# Power.net
KiCad netlist of a schematic drawn in Altium Designer
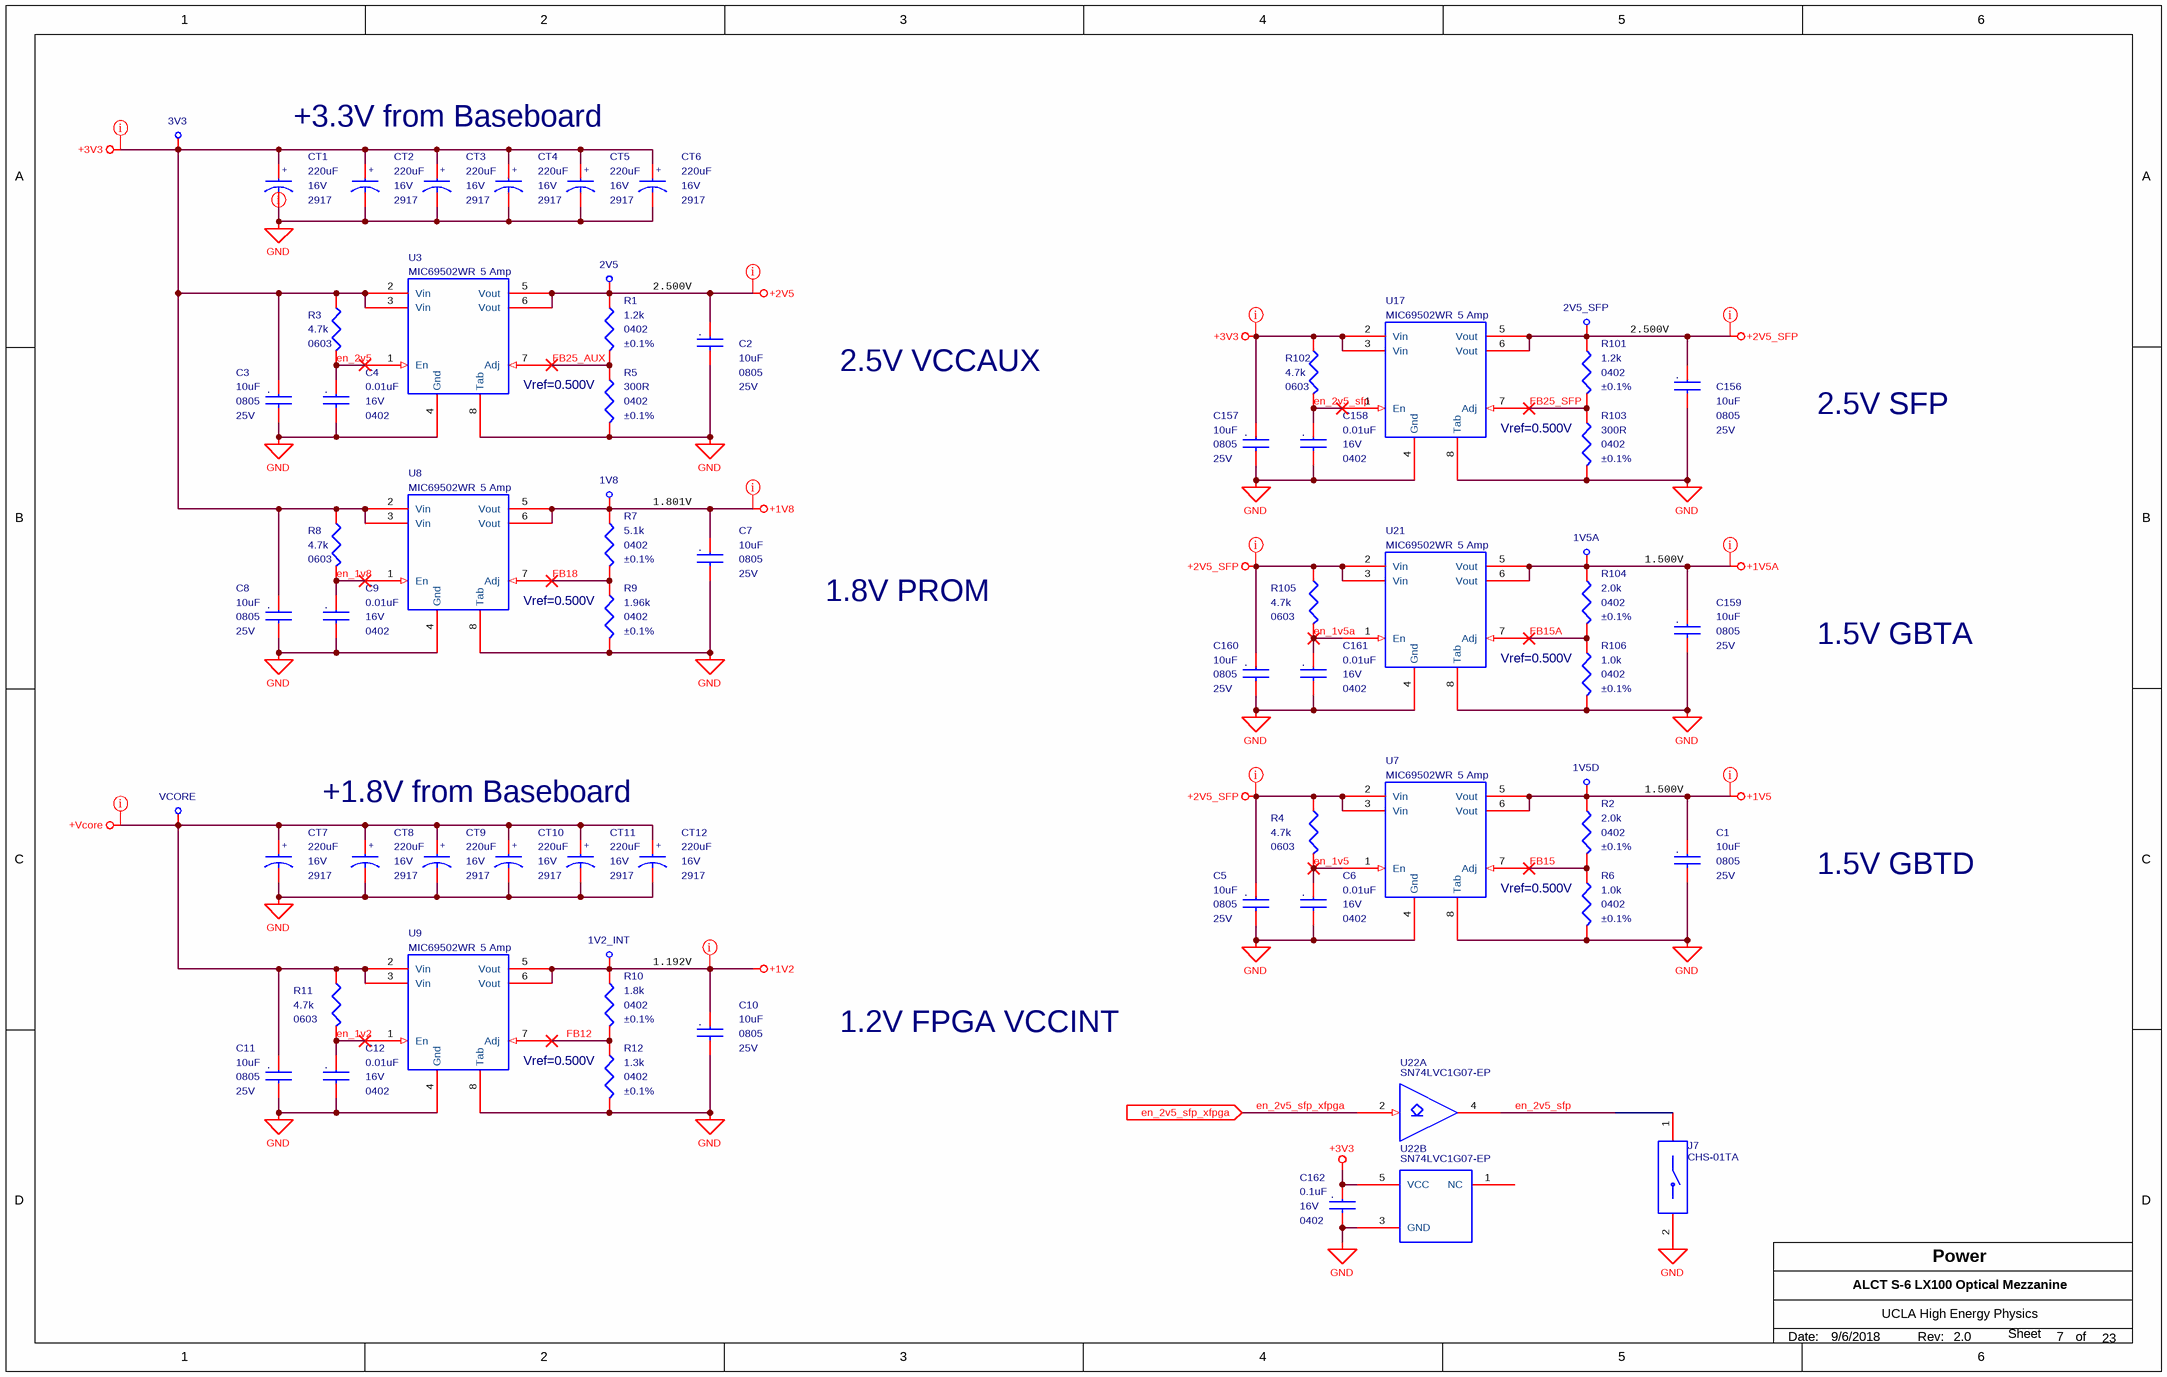
[diagram p0: Power.SchDoc]

(export (version "E")
  (design (tool "Eeschema 10.0.6"))
  (components
    (comp (ref "1V2_INT")
      (value "Test Point Via")
      (footprint "MC_S6/TH/TPVIA")
      (libsource (lib "ALCT_MEZ_SPARTAN6_Library") (part "TPVIA"))
    )
    (comp (ref "1V5A")
      (value "Test Point Via")
      (footprint "MC_S6/TH/TPVIA")
      (libsource (lib "ALCT_MEZ_SPARTAN6_Library") (part "TPVIA"))
    )
    (comp (ref "1V5D")
      (value "Test Point Via")
      (footprint "MC_S6/TH/TPVIA")
      (libsource (lib "ALCT_MEZ_SPARTAN6_Library") (part "TPVIA"))
    )
    (comp (ref "1V8")
      (value "Test Point Via")
      (footprint "MC_S6/TH/TPVIA")
      (libsource (lib "ALCT_MEZ_SPARTAN6_Library") (part "TPVIA"))
    )
    (comp (ref "2V5")
      (value "Test Point Via")
      (footprint "MC_S6/TH/TPVIA")
      (libsource (lib "ALCT_MEZ_SPARTAN6_Library") (part "TPVIA"))
    )
    (comp (ref "2V5_SFP")
      (value "Test Point Via")
      (footprint "MC_S6/TH/TPVIA")
      (libsource (lib "ALCT_MEZ_SPARTAN6_Library") (part "TPVIA"))
    )
    (comp (ref "3V3")
      (value "Test Point Via")
      (footprint "MC_S6/TH/TPVIA")
      (libsource (lib "ALCT_MEZ_SPARTAN6_Library") (part "TPVIA"))
    )
    (comp (ref "C1")
      (value "10uF")
      (footprint "MC_S6/SM/C_0805_IPC")
      (description "CAP CER 10UF 25V X5R 0805")
      (fields
        (field (name "MANUFACTURER") "Murata Electronics North America")
        (field (name "MANUFACTURER PART NUMBER") "GRM21BR61E106KA73L")
        (field (name "VOLTAGE - RATED") "25V")
        (field (name "PACKAGE") "0805")
      )
      (libsource (lib "ALCT_MEZ_SPARTAN6_Library") (part "GRM21BR61E106KA73L"))
    )
    (comp (ref "C2")
      (value "10uF")
      (footprint "MC_S6/SM/C_0805_IPC")
      (description "CAP CER 10UF 25V X5R 0805")
      (fields
        (field (name "MANUFACTURER") "Murata Electronics North America")
        (field (name "MANUFACTURER PART NUMBER") "GRM21BR61E106KA73L")
        (field (name "VOLTAGE - RATED") "25V")
        (field (name "PACKAGE") "0805")
      )
      (libsource (lib "ALCT_MEZ_SPARTAN6_Library") (part "GRM21BR61E106KA73L"))
    )
    (comp (ref "C3")
      (value "10uF")
      (footprint "MC_S6/SM/C_0805_IPC")
      (description "CAP CER 10UF 25V X5R 0805")
      (fields
        (field (name "MANUFACTURER") "Murata Electronics North America")
        (field (name "MANUFACTURER PART NUMBER") "GRM21BR61E106KA73L")
        (field (name "VOLTAGE - RATED") "25V")
        (field (name "PACKAGE") "0805")
      )
      (libsource (lib "ALCT_MEZ_SPARTAN6_Library") (part "GRM21BR61E106KA73L"))
    )
    (comp (ref "C4")
      (value "0.01uF")
      (footprint "MC_S6/SM/C_0402_IPC")
      (description "CAP CER 10nF 16V X7R 0402")
      (fields
        (field (name "MANUFACTURER") "KEMET")
        (field (name "MANUFACTURER PART NUMBER") "C0402C103K4RACTU")
        (field (name "VOLTAGE - RATED") "16V")
        (field (name "PACKAGE") "0402")
      )
      (libsource (lib "ALCT_MEZ_SPARTAN6_Library") (part "C0402C103K4RACTU"))
    )
    (comp (ref "C5")
      (value "10uF")
      (footprint "MC_S6/SM/C_0805_IPC")
      (description "CAP CER 10UF 25V X5R 0805")
      (fields
        (field (name "MANUFACTURER") "Murata Electronics North America")
        (field (name "MANUFACTURER PART NUMBER") "GRM21BR61E106KA73L")
        (field (name "VOLTAGE - RATED") "25V")
        (field (name "PACKAGE") "0805")
      )
      (libsource (lib "ALCT_MEZ_SPARTAN6_Library") (part "GRM21BR61E106KA73L"))
    )
    (comp (ref "C6")
      (value "0.01uF")
      (footprint "MC_S6/SM/C_0402_IPC")
      (description "CAP CER 10nF 16V X7R 0402")
      (fields
        (field (name "MANUFACTURER") "KEMET")
        (field (name "MANUFACTURER PART NUMBER") "C0402C103K4RACTU")
        (field (name "VOLTAGE - RATED") "16V")
        (field (name "PACKAGE") "0402")
      )
      (libsource (lib "ALCT_MEZ_SPARTAN6_Library") (part "C0402C103K4RACTU"))
    )
    (comp (ref "C7")
      (value "10uF")
      (footprint "MC_S6/SM/C_0805_IPC")
      (description "CAP CER 10UF 25V X5R 0805")
      (fields
        (field (name "MANUFACTURER") "Murata Electronics North America")
        (field (name "MANUFACTURER PART NUMBER") "GRM21BR61E106KA73L")
        (field (name "VOLTAGE - RATED") "25V")
        (field (name "PACKAGE") "0805")
      )
      (libsource (lib "ALCT_MEZ_SPARTAN6_Library") (part "GRM21BR61E106KA73L"))
    )
    (comp (ref "C8")
      (value "10uF")
      (footprint "MC_S6/SM/C_0805_IPC")
      (description "CAP CER 10UF 25V X5R 0805")
      (fields
        (field (name "MANUFACTURER") "Murata Electronics North America")
        (field (name "MANUFACTURER PART NUMBER") "GRM21BR61E106KA73L")
        (field (name "VOLTAGE - RATED") "25V")
        (field (name "PACKAGE") "0805")
      )
      (libsource (lib "ALCT_MEZ_SPARTAN6_Library") (part "GRM21BR61E106KA73L"))
    )
    (comp (ref "C9")
      (value "0.01uF")
      (footprint "MC_S6/SM/C_0402_IPC")
      (description "CAP CER 10nF 16V X7R 0402")
      (fields
        (field (name "MANUFACTURER") "KEMET")
        (field (name "MANUFACTURER PART NUMBER") "C0402C103K4RACTU")
        (field (name "VOLTAGE - RATED") "16V")
        (field (name "PACKAGE") "0402")
      )
      (libsource (lib "ALCT_MEZ_SPARTAN6_Library") (part "C0402C103K4RACTU"))
    )
    (comp (ref "C10")
      (value "10uF")
      (footprint "MC_S6/SM/C_0805_IPC")
      (description "CAP CER 10UF 25V X5R 0805")
      (fields
        (field (name "MANUFACTURER") "Murata Electronics North America")
        (field (name "MANUFACTURER PART NUMBER") "GRM21BR61E106KA73L")
        (field (name "VOLTAGE - RATED") "25V")
        (field (name "PACKAGE") "0805")
      )
      (libsource (lib "ALCT_MEZ_SPARTAN6_Library") (part "GRM21BR61E106KA73L"))
    )
    (comp (ref "C11")
      (value "10uF")
      (footprint "MC_S6/SM/C_0805_IPC")
      (description "CAP CER 10UF 25V X5R 0805")
      (fields
        (field (name "MANUFACTURER") "Murata Electronics North America")
        (field (name "MANUFACTURER PART NUMBER") "GRM21BR61E106KA73L")
        (field (name "VOLTAGE - RATED") "25V")
        (field (name "PACKAGE") "0805")
      )
      (libsource (lib "ALCT_MEZ_SPARTAN6_Library") (part "GRM21BR61E106KA73L"))
    )
    (comp (ref "C12")
      (value "0.01uF")
      (footprint "MC_S6/SM/C_0402_IPC")
      (description "CAP CER 10nF 16V X7R 0402")
      (fields
        (field (name "MANUFACTURER") "KEMET")
        (field (name "MANUFACTURER PART NUMBER") "C0402C103K4RACTU")
        (field (name "VOLTAGE - RATED") "16V")
        (field (name "PACKAGE") "0402")
      )
      (libsource (lib "ALCT_MEZ_SPARTAN6_Library") (part "C0402C103K4RACTU"))
    )
    (comp (ref "C156")
      (value "10uF")
      (footprint "MC_S6/SM/C_0805_IPC")
      (description "CAP CER 10UF 25V X5R 0805")
      (fields
        (field (name "MANUFACTURER") "Murata Electronics North America")
        (field (name "MANUFACTURER PART NUMBER") "GRM21BR61E106KA73L")
        (field (name "VOLTAGE - RATED") "25V")
        (field (name "PACKAGE") "0805")
      )
      (libsource (lib "ALCT_MEZ_SPARTAN6_Library") (part "GRM21BR61E106KA73L"))
    )
    (comp (ref "C157")
      (value "10uF")
      (footprint "MC_S6/SM/C_0805_IPC")
      (description "CAP CER 10UF 25V X5R 0805")
      (fields
        (field (name "MANUFACTURER") "Murata Electronics North America")
        (field (name "MANUFACTURER PART NUMBER") "GRM21BR61E106KA73L")
        (field (name "VOLTAGE - RATED") "25V")
        (field (name "PACKAGE") "0805")
      )
      (libsource (lib "ALCT_MEZ_SPARTAN6_Library") (part "GRM21BR61E106KA73L"))
    )
    (comp (ref "C158")
      (value "0.01uF")
      (footprint "MC_S6/SM/C_0402_IPC")
      (description "CAP CER 10nF 16V X7R 0402")
      (fields
        (field (name "MANUFACTURER") "KEMET")
        (field (name "MANUFACTURER PART NUMBER") "C0402C103K4RACTU")
        (field (name "VOLTAGE - RATED") "16V")
        (field (name "PACKAGE") "0402")
      )
      (libsource (lib "ALCT_MEZ_SPARTAN6_Library") (part "C0402C103K4RACTU"))
    )
    (comp (ref "C159")
      (value "10uF")
      (footprint "MC_S6/SM/C_0805_IPC")
      (description "CAP CER 10UF 25V X5R 0805")
      (fields
        (field (name "MANUFACTURER") "Murata Electronics North America")
        (field (name "MANUFACTURER PART NUMBER") "GRM21BR61E106KA73L")
        (field (name "VOLTAGE - RATED") "25V")
        (field (name "PACKAGE") "0805")
      )
      (libsource (lib "ALCT_MEZ_SPARTAN6_Library") (part "GRM21BR61E106KA73L"))
    )
    (comp (ref "C160")
      (value "10uF")
      (footprint "MC_S6/SM/C_0805_IPC")
      (description "CAP CER 10UF 25V X5R 0805")
      (fields
        (field (name "MANUFACTURER") "Murata Electronics North America")
        (field (name "MANUFACTURER PART NUMBER") "GRM21BR61E106KA73L")
        (field (name "VOLTAGE - RATED") "25V")
        (field (name "PACKAGE") "0805")
      )
      (libsource (lib "ALCT_MEZ_SPARTAN6_Library") (part "GRM21BR61E106KA73L"))
    )
    (comp (ref "C161")
      (value "0.01uF")
      (footprint "MC_S6/SM/C_0402_IPC")
      (description "CAP CER 10nF 16V X7R 0402")
      (fields
        (field (name "MANUFACTURER") "KEMET")
        (field (name "MANUFACTURER PART NUMBER") "C0402C103K4RACTU")
        (field (name "VOLTAGE - RATED") "16V")
        (field (name "PACKAGE") "0402")
      )
      (libsource (lib "ALCT_MEZ_SPARTAN6_Library") (part "C0402C103K4RACTU"))
    )
    (comp (ref "C162")
      (value "0.1uF")
      (footprint "MC_S6/SM/C_0402_IPC")
      (description "CAP CER 0.1UF 16V X7R 0402")
      (fields
        (field (name "MANUFACTURER") "KEMET")
        (field (name "MANUFACTURER PART NUMBER") "C0402C104K4RACTU")
        (field (name "PACKAGE") "0402")
        (field (name "VOLTAGE - RATED") "16V")
      )
      (libsource (lib "ALCT_MEZ_SPARTAN6_Library") (part "C0402C104K4RACTU"))
    )
    (comp (ref "CT1")
      (value "220uF")
      (footprint "MC_S6/SM/CT_2917_D")
      (description "CAP TANT 220UF 16V 10% 2917")
      (fields
        (field (name "MANUFACTURER") "KEMET")
        (field (name "MANUFACTURER PART NUMBER") "T491D227K016AT")
        (field (name "VOLTAGE - RATED") "16V")
        (field (name "PACKAGE") "2917")
      )
      (libsource (lib "ALCT_MEZ_SPARTAN6_Library") (part "T491D227K016AT"))
    )
    (comp (ref "CT2")
      (value "220uF")
      (footprint "MC_S6/SM/CT_2917_D")
      (description "CAP TANT 220UF 16V 10% 2917")
      (fields
        (field (name "MANUFACTURER") "KEMET")
        (field (name "MANUFACTURER PART NUMBER") "T491D227K016AT")
        (field (name "VOLTAGE - RATED") "16V")
        (field (name "PACKAGE") "2917")
      )
      (libsource (lib "ALCT_MEZ_SPARTAN6_Library") (part "T491D227K016AT"))
    )
    (comp (ref "CT3")
      (value "220uF")
      (footprint "MC_S6/SM/CT_2917_D")
      (description "CAP TANT 220UF 16V 10% 2917")
      (fields
        (field (name "MANUFACTURER") "KEMET")
        (field (name "MANUFACTURER PART NUMBER") "T491D227K016AT")
        (field (name "VOLTAGE - RATED") "16V")
        (field (name "PACKAGE") "2917")
      )
      (libsource (lib "ALCT_MEZ_SPARTAN6_Library") (part "T491D227K016AT"))
    )
    (comp (ref "CT4")
      (value "220uF")
      (footprint "MC_S6/SM/CT_2917_D")
      (description "CAP TANT 220UF 16V 10% 2917")
      (fields
        (field (name "MANUFACTURER") "KEMET")
        (field (name "MANUFACTURER PART NUMBER") "T491D227K016AT")
        (field (name "VOLTAGE - RATED") "16V")
        (field (name "PACKAGE") "2917")
      )
      (libsource (lib "ALCT_MEZ_SPARTAN6_Library") (part "T491D227K016AT"))
    )
    (comp (ref "CT5")
      (value "220uF")
      (footprint "MC_S6/SM/CT_2917_D")
      (description "CAP TANT 220UF 16V 10% 2917")
      (fields
        (field (name "MANUFACTURER") "KEMET")
        (field (name "MANUFACTURER PART NUMBER") "T491D227K016AT")
        (field (name "VOLTAGE - RATED") "16V")
        (field (name "PACKAGE") "2917")
      )
      (libsource (lib "ALCT_MEZ_SPARTAN6_Library") (part "T491D227K016AT"))
    )
    (comp (ref "CT6")
      (value "220uF")
      (footprint "MC_S6/SM/CT_2917_D")
      (description "CAP TANT 220UF 16V 10% 2917")
      (fields
        (field (name "MANUFACTURER") "KEMET")
        (field (name "MANUFACTURER PART NUMBER") "T491D227K016AT")
        (field (name "VOLTAGE - RATED") "16V")
        (field (name "PACKAGE") "2917")
      )
      (libsource (lib "ALCT_MEZ_SPARTAN6_Library") (part "T491D227K016AT"))
    )
    (comp (ref "CT7")
      (value "220uF")
      (footprint "MC_S6/SM/CT_2917_D")
      (description "CAP TANT 220UF 16V 10% 2917")
      (fields
        (field (name "MANUFACTURER") "KEMET")
        (field (name "MANUFACTURER PART NUMBER") "T491D227K016AT")
        (field (name "VOLTAGE - RATED") "16V")
        (field (name "PACKAGE") "2917")
      )
      (libsource (lib "ALCT_MEZ_SPARTAN6_Library") (part "T491D227K016AT"))
    )
    (comp (ref "CT8")
      (value "220uF")
      (footprint "MC_S6/SM/CT_2917_D")
      (description "CAP TANT 220UF 16V 10% 2917")
      (fields
        (field (name "MANUFACTURER") "KEMET")
        (field (name "MANUFACTURER PART NUMBER") "T491D227K016AT")
        (field (name "VOLTAGE - RATED") "16V")
        (field (name "PACKAGE") "2917")
      )
      (libsource (lib "ALCT_MEZ_SPARTAN6_Library") (part "T491D227K016AT"))
    )
    (comp (ref "CT9")
      (value "220uF")
      (footprint "MC_S6/SM/CT_2917_D")
      (description "CAP TANT 220UF 16V 10% 2917")
      (fields
        (field (name "MANUFACTURER") "KEMET")
        (field (name "MANUFACTURER PART NUMBER") "T491D227K016AT")
        (field (name "VOLTAGE - RATED") "16V")
        (field (name "PACKAGE") "2917")
      )
      (libsource (lib "ALCT_MEZ_SPARTAN6_Library") (part "T491D227K016AT"))
    )
    (comp (ref "CT10")
      (value "220uF")
      (footprint "MC_S6/SM/CT_2917_D")
      (description "CAP TANT 220UF 16V 10% 2917")
      (fields
        (field (name "MANUFACTURER") "KEMET")
        (field (name "MANUFACTURER PART NUMBER") "T491D227K016AT")
        (field (name "VOLTAGE - RATED") "16V")
        (field (name "PACKAGE") "2917")
      )
      (libsource (lib "ALCT_MEZ_SPARTAN6_Library") (part "T491D227K016AT"))
    )
    (comp (ref "CT11")
      (value "220uF")
      (footprint "MC_S6/SM/CT_2917_D")
      (description "CAP TANT 220UF 16V 10% 2917")
      (fields
        (field (name "MANUFACTURER") "KEMET")
        (field (name "MANUFACTURER PART NUMBER") "T491D227K016AT")
        (field (name "VOLTAGE - RATED") "16V")
        (field (name "PACKAGE") "2917")
      )
      (libsource (lib "ALCT_MEZ_SPARTAN6_Library") (part "T491D227K016AT"))
    )
    (comp (ref "CT12")
      (value "220uF")
      (footprint "MC_S6/SM/CT_2917_D")
      (description "CAP TANT 220UF 16V 10% 2917")
      (fields
        (field (name "MANUFACTURER") "KEMET")
        (field (name "MANUFACTURER PART NUMBER") "T491D227K016AT")
        (field (name "VOLTAGE - RATED") "16V")
        (field (name "PACKAGE") "2917")
      )
      (libsource (lib "ALCT_MEZ_SPARTAN6_Library") (part "T491D227K016AT"))
    )
    (comp (ref "J7")
      (value "CHS-01TA")
      (footprint "CHS-01TA")
      (description "SWITCH SLIDE DIP SPST 100MA 6V")
      (fields (field (name "MANUFACTURER") "Nidec Copal"))
      (libsource (lib "ALCT_MEZ_SPARTAN6_Library") (part "CHS-01TA"))
    )
    (comp (ref "R1")
      (value "1.2k")
      (footprint "MC_S6/SM/R_0402_IPC")
      (description "RES SMD 1.2K OHM 0.1% 1/16W 0402")
      (fields
        (field (name "TOLERANCE") "±0.1%")
        (field (name "MANUFACTURER") "Panasonic Electronic Components")
        (field (name "MANUFACTURER PART NUMBER") "ERA-2AEB122X")
        (field (name "PACKAGE") "0402")
      )
      (libsource (lib "ALCT_MEZ_SPARTAN6_Library") (part "ERA-2AEB122X"))
    )
    (comp (ref "R2")
      (value "2.0k")
      (footprint "MC_S6/SM/R_0402_IPC")
      (description "RES SMD 2.0K OHM 0.1% 1/16W 0402")
      (fields
        (field (name "TOLERANCE") "±0.1%")
        (field (name "MANUFACTURER") "Panasonic Electronic Components")
        (field (name "MANUFACTURER PART NUMBER") "ERA-2AEB202X")
        (field (name "PACKAGE") "0402")
      )
      (libsource (lib "ALCT_MEZ_SPARTAN6_Library") (part "ERA-2AEB202X"))
    )
    (comp (ref "R3")
      (value "4.7k")
      (footprint "MC_S6/SM/R_0603_IPC")
      (description "RES SMD 4.7K OHM 1% 1/10W 0603")
      (fields
        (field (name "TOLERANCE") "±1%")
        (field (name "MANUFACTURER") "Bourns Inc.")
        (field (name "SUPPLIER DEVICE PACKAGE") "0603")
      )
      (libsource (lib "ALCT_MEZ_SPARTAN6_Library") (part "CR0603-FX-4701ELF"))
    )
    (comp (ref "R4")
      (value "4.7k")
      (footprint "MC_S6/SM/R_0603_IPC")
      (description "RES SMD 4.7K OHM 1% 1/10W 0603")
      (fields
        (field (name "TOLERANCE") "±1%")
        (field (name "MANUFACTURER") "Bourns Inc.")
        (field (name "SUPPLIER DEVICE PACKAGE") "0603")
      )
      (libsource (lib "ALCT_MEZ_SPARTAN6_Library") (part "CR0603-FX-4701ELF"))
    )
    (comp (ref "R5")
      (value "300R")
      (footprint "MC_S6/SM/R_0402_IPC")
      (description "RES SMD 300 OHM 0.1% 1/16W 0402")
      (fields
        (field (name "TOLERANCE") "±0.1%")
        (field (name "MANUFACTURER") "Panasonic Electronic Components")
        (field (name "MANUFACTURER PART NUMBER") "ERA-2AEB301X")
        (field (name "PACKAGE") "0402")
      )
      (libsource (lib "ALCT_MEZ_SPARTAN6_Library") (part "ERA-2AEB301X"))
    )
    (comp (ref "R6")
      (value "1.0k")
      (footprint "MC_S6/SM/R_0402_IPC")
      (description "RES SMD 1.0K OHM 0.1% 1/16W 0402")
      (fields
        (field (name "TOLERANCE") "±0.1%")
        (field (name "MANUFACTURER") "Panasonic Electronic Components")
        (field (name "MANUFACTURER PART NUMBER") "ERA-2AEB102X")
        (field (name "PACKAGE") "0402")
      )
      (libsource (lib "ALCT_MEZ_SPARTAN6_Library") (part "ERA-2AEB102X"))
    )
    (comp (ref "R7")
      (value "5.1k")
      (footprint "MC_S6/SM/R_0402_IPC")
      (description "RES SMD 5.1K OHM 0.1% 1/16W 0402")
      (fields
        (field (name "TOLERANCE") "±0.1%")
        (field (name "MANUFACTURER") "Panasonic Electronic Components")
        (field (name "MANUFACTURER PART NUMBER") "ERA-2AEB512X")
        (field (name "SUPPLIER DEVICE PACKAGE") "0402")
      )
      (libsource (lib "ALCT_MEZ_SPARTAN6_Library") (part "ERA-2AEB512X"))
    )
    (comp (ref "R8")
      (value "4.7k")
      (footprint "MC_S6/SM/R_0603_IPC")
      (description "RES SMD 4.7K OHM 1% 1/10W 0603")
      (fields
        (field (name "TOLERANCE") "±1%")
        (field (name "MANUFACTURER") "Bourns Inc.")
        (field (name "SUPPLIER DEVICE PACKAGE") "0603")
      )
      (libsource (lib "ALCT_MEZ_SPARTAN6_Library") (part "CR0603-FX-4701ELF"))
    )
    (comp (ref "R9")
      (value "1.96k")
      (footprint "MC_S6/SM/R_0402_IPC")
      (description "RES SMD 1.96K OHM 0.1% 1/16W 0402")
      (fields
        (field (name "TOLERANCE") "±0.1%")
        (field (name "MANUFACTURER") "Panasonic Electronic Components")
        (field (name "MANUFACTURER PART NUMBER") "ERA-2AEB1961X")
        (field (name "PACKAGE") "0402")
      )
      (libsource (lib "ALCT_MEZ_SPARTAN6_Library") (part "ERA-2AEB1961X"))
    )
    (comp (ref "R10")
      (value "1.8k")
      (footprint "MC_S6/SM/R_0402_IPC")
      (description "RES SMD 1.8k OHM 0.1% 1/16W 0402")
      (fields
        (field (name "TOLERANCE") "±0.1%")
        (field (name "MANUFACTURER") "Panasonic Electronic Components")
        (field (name "MANUFACTURER PART NUMBER") "ERA-2AEB182X")
        (field (name "SUPPLIER DEVICE PACKAGE") "0402")
      )
      (libsource (lib "ALCT_MEZ_SPARTAN6_Library") (part "ERA-2AEB182X"))
    )
    (comp (ref "R11")
      (value "4.7k")
      (footprint "MC_S6/SM/R_0603_IPC")
      (description "RES SMD 4.7K OHM 1% 1/10W 0603")
      (fields
        (field (name "TOLERANCE") "±1%")
        (field (name "MANUFACTURER") "Bourns Inc.")
        (field (name "SUPPLIER DEVICE PACKAGE") "0603")
      )
      (libsource (lib "ALCT_MEZ_SPARTAN6_Library") (part "CR0603-FX-4701ELF"))
    )
    (comp (ref "R12")
      (value "1.3k")
      (footprint "MC_S6/SM/R_0402_IPC")
      (description "RES SMD 1.3k OHM 0.1% 1/16W 0402")
      (fields
        (field (name "TOLERANCE") "±0.1%")
        (field (name "MANUFACTURER") "Panasonic Electronic Components")
        (field (name "MANUFACTURER PART NUMBER") "ERA-2AEB132X")
        (field (name "SUPPLIER DEVICE PACKAGE") "0402")
      )
      (libsource (lib "ALCT_MEZ_SPARTAN6_Library") (part "ERA-2AEB132X"))
    )
    (comp (ref "R101")
      (value "1.2k")
      (footprint "MC_S6/SM/R_0402_IPC")
      (description "RES SMD 1.2K OHM 0.1% 1/16W 0402")
      (fields
        (field (name "TOLERANCE") "±0.1%")
        (field (name "MANUFACTURER") "Panasonic Electronic Components")
        (field (name "MANUFACTURER PART NUMBER") "ERA-2AEB122X")
        (field (name "PACKAGE") "0402")
      )
      (libsource (lib "ALCT_MEZ_SPARTAN6_Library") (part "ERA-2AEB122X"))
    )
    (comp (ref "R102")
      (value "4.7k")
      (footprint "MC_S6/SM/R_0603_IPC")
      (description "RES SMD 4.7K OHM 1% 1/10W 0603")
      (fields
        (field (name "TOLERANCE") "±1%")
        (field (name "MANUFACTURER") "Bourns Inc.")
        (field (name "SUPPLIER DEVICE PACKAGE") "0603")
      )
      (libsource (lib "ALCT_MEZ_SPARTAN6_Library") (part "CR0603-FX-4701ELF"))
    )
    (comp (ref "R103")
      (value "300R")
      (footprint "MC_S6/SM/R_0402_IPC")
      (description "RES SMD 300 OHM 0.1% 1/16W 0402")
      (fields
        (field (name "TOLERANCE") "±0.1%")
        (field (name "MANUFACTURER") "Panasonic Electronic Components")
        (field (name "MANUFACTURER PART NUMBER") "ERA-2AEB301X")
        (field (name "PACKAGE") "0402")
      )
      (libsource (lib "ALCT_MEZ_SPARTAN6_Library") (part "ERA-2AEB301X"))
    )
    (comp (ref "R104")
      (value "2.0k")
      (footprint "MC_S6/SM/R_0402_IPC")
      (description "RES SMD 2.0K OHM 0.1% 1/16W 0402")
      (fields
        (field (name "TOLERANCE") "±0.1%")
        (field (name "MANUFACTURER") "Panasonic Electronic Components")
        (field (name "MANUFACTURER PART NUMBER") "ERA-2AEB202X")
        (field (name "PACKAGE") "0402")
      )
      (libsource (lib "ALCT_MEZ_SPARTAN6_Library") (part "ERA-2AEB202X"))
    )
    (comp (ref "R105")
      (value "4.7k")
      (footprint "MC_S6/SM/R_0603_IPC")
      (description "RES SMD 4.7K OHM 1% 1/10W 0603")
      (fields
        (field (name "TOLERANCE") "±1%")
        (field (name "MANUFACTURER") "Bourns Inc.")
        (field (name "SUPPLIER DEVICE PACKAGE") "0603")
      )
      (libsource (lib "ALCT_MEZ_SPARTAN6_Library") (part "CR0603-FX-4701ELF"))
    )
    (comp (ref "R106")
      (value "1.0k")
      (footprint "MC_S6/SM/R_0402_IPC")
      (description "RES SMD 1.0K OHM 0.1% 1/16W 0402")
      (fields
        (field (name "TOLERANCE") "±0.1%")
        (field (name "MANUFACTURER") "Panasonic Electronic Components")
        (field (name "MANUFACTURER PART NUMBER") "ERA-2AEB102X")
        (field (name "PACKAGE") "0402")
      )
      (libsource (lib "ALCT_MEZ_SPARTAN6_Library") (part "ERA-2AEB102X"))
    )
    (comp (ref "U3")
      (value "MIC69502WR")
      (footprint "MC_S6/SM/SPAK7")
      (description "IC REG LDO ADJ 5A SPAK-7")
      (fields (field (name "MANUFACTURER") "Microchip Technology"))
      (libsource (lib "ALCT_MEZ_SPARTAN6_Library") (part "MIC69502WR"))
    )
    (comp (ref "U7")
      (value "MIC69502WR")
      (footprint "MC_S6/SM/SPAK7")
      (description "IC REG LDO ADJ 5A SPAK-7")
      (fields (field (name "MANUFACTURER") "Microchip Technology"))
      (libsource (lib "ALCT_MEZ_SPARTAN6_Library") (part "MIC69502WR"))
    )
    (comp (ref "U8")
      (value "MIC69502WR")
      (footprint "MC_S6/SM/SPAK7")
      (description "IC REG LDO ADJ 5A SPAK-7")
      (fields (field (name "MANUFACTURER") "Microchip Technology"))
      (libsource (lib "ALCT_MEZ_SPARTAN6_Library") (part "MIC69502WR"))
    )
    (comp (ref "U9")
      (value "MIC69502WR")
      (footprint "MC_S6/SM/SPAK7")
      (description "IC REG LDO ADJ 5A SPAK-7")
      (fields (field (name "MANUFACTURER") "Microchip Technology"))
      (libsource (lib "ALCT_MEZ_SPARTAN6_Library") (part "MIC69502WR"))
    )
    (comp (ref "U17")
      (value "MIC69502WR")
      (footprint "MC_S6/SM/SPAK7")
      (description "IC REG LDO ADJ 5A SPAK-7")
      (fields (field (name "MANUFACTURER") "Microchip Technology"))
      (libsource (lib "ALCT_MEZ_SPARTAN6_Library") (part "MIC69502WR"))
    )
    (comp (ref "U21")
      (value "MIC69502WR")
      (footprint "MC_S6/SM/SPAK7")
      (description "IC REG LDO ADJ 5A SPAK-7")
      (fields (field (name "MANUFACTURER") "Microchip Technology"))
      (libsource (lib "ALCT_MEZ_SPARTAN6_Library") (part "MIC69502WR"))
    )
    (comp (ref "U22")
      (value "SN74LVC1G07-EP")
      (footprint "SOT353-1")
      (description "IC BUFF/DVR NON-INVERT Open Drain SC70-5")
      (fields
        (field (name "MANUFACTURER") "Texas Instruments")
        (field (name "MANUFACTURER PART NUMBER") "SN74LVC1G07MDCKREP")
      )
      (libsource (lib "ALCT_MEZ_SPARTAN6_Library") (part "SN74LVC1G07-EP"))
    )
    (comp (ref "VCORE")
      (value "Test Point Via")
      (footprint "MC_S6/TH/TPVIA")
      (libsource (lib "ALCT_MEZ_SPARTAN6_Library") (part "TPVIA"))
    )
  )
  (nets
    (net (code "1") (name "+1V2") (class "Default")
      (node (ref "1V2_INT") (pin "1") (pinfunction "In_1") (pintype "passive"))
      (node (ref "C10") (pin "1") (pinfunction "1_1") (pintype "passive"))
      (node (ref "R10") (pin "1") (pinfunction "1_1") (pintype "passive"))
      (node (ref "U9") (pin "5") (pinfunction "Vout_5") (pintype "power_in"))
      (node (ref "U9") (pin "6") (pinfunction "Vout_6") (pintype "power_in"))
    )
    (net (code "2") (name "+1V5") (class "Default")
      (node (ref "1V5D") (pin "1") (pinfunction "In_1") (pintype "passive"))
      (node (ref "C1") (pin "1") (pinfunction "1_1") (pintype "passive"))
      (node (ref "R2") (pin "1") (pinfunction "1_1") (pintype "passive"))
      (node (ref "U7") (pin "5") (pinfunction "Vout_5") (pintype "power_in"))
      (node (ref "U7") (pin "6") (pinfunction "Vout_6") (pintype "power_in"))
    )
    (net (code "3") (name "+1V5A") (class "Default")
      (node (ref "1V5A") (pin "1") (pinfunction "In_1") (pintype "passive"))
      (node (ref "C159") (pin "1") (pinfunction "1_1") (pintype "passive"))
      (node (ref "R104") (pin "1") (pinfunction "1_1") (pintype "passive"))
      (node (ref "U21") (pin "5") (pinfunction "Vout_5") (pintype "power_in"))
      (node (ref "U21") (pin "6") (pinfunction "Vout_6") (pintype "power_in"))
    )
    (net (code "4") (name "+1V8") (class "Default")
      (node (ref "1V8") (pin "1") (pinfunction "In_1") (pintype "passive"))
      (node (ref "C7") (pin "1") (pinfunction "1_1") (pintype "passive"))
      (node (ref "R7") (pin "1") (pinfunction "1_1") (pintype "passive"))
      (node (ref "U8") (pin "5") (pinfunction "Vout_5") (pintype "power_in"))
      (node (ref "U8") (pin "6") (pinfunction "Vout_6") (pintype "power_in"))
    )
    (net (code "5") (name "+2V5") (class "Default")
      (node (ref "2V5") (pin "1") (pinfunction "In_1") (pintype "passive"))
      (node (ref "C2") (pin "1") (pinfunction "1_1") (pintype "passive"))
      (node (ref "R1") (pin "1") (pinfunction "1_1") (pintype "passive"))
      (node (ref "U3") (pin "5") (pinfunction "Vout_5") (pintype "power_in"))
      (node (ref "U3") (pin "6") (pinfunction "Vout_6") (pintype "power_in"))
    )
    (net (code "6") (name "+2V5_SFP") (class "Default")
      (node (ref "2V5_SFP") (pin "1") (pinfunction "In_1") (pintype "passive"))
      (node (ref "C156") (pin "1") (pinfunction "1_1") (pintype "passive"))
      (node (ref "C160") (pin "1") (pinfunction "1_1") (pintype "passive"))
      (node (ref "C5") (pin "1") (pinfunction "1_1") (pintype "passive"))
      (node (ref "R101") (pin "1") (pinfunction "1_1") (pintype "passive"))
      (node (ref "R105") (pin "1") (pinfunction "1_1") (pintype "passive"))
      (node (ref "R4") (pin "1") (pinfunction "1_1") (pintype "passive"))
      (node (ref "U17") (pin "5") (pinfunction "Vout_5") (pintype "power_in"))
      (node (ref "U17") (pin "6") (pinfunction "Vout_6") (pintype "power_in"))
      (node (ref "U21") (pin "2") (pinfunction "Vin_2") (pintype "power_in"))
      (node (ref "U21") (pin "3") (pinfunction "Vin_3") (pintype "power_in"))
      (node (ref "U7") (pin "2") (pinfunction "Vin_2") (pintype "power_in"))
      (node (ref "U7") (pin "3") (pinfunction "Vin_3") (pintype "power_in"))
    )
    (net (code "7") (name "+3V3") (class "Default")
      (node (ref "3V3") (pin "1") (pinfunction "In_1") (pintype "passive"))
      (node (ref "C157") (pin "1") (pinfunction "1_1") (pintype "passive"))
      (node (ref "C162") (pin "1") (pinfunction "1_1") (pintype "passive"))
      (node (ref "C3") (pin "1") (pinfunction "1_1") (pintype "passive"))
      (node (ref "C8") (pin "1") (pinfunction "1_1") (pintype "passive"))
      (node (ref "CT1") (pin "1") (pinfunction "1_1") (pintype "passive"))
      (node (ref "CT2") (pin "1") (pinfunction "1_1") (pintype "passive"))
      (node (ref "CT3") (pin "1") (pinfunction "1_1") (pintype "passive"))
      (node (ref "CT4") (pin "1") (pinfunction "1_1") (pintype "passive"))
      (node (ref "CT5") (pin "1") (pinfunction "1_1") (pintype "passive"))
      (node (ref "CT6") (pin "1") (pinfunction "1_1") (pintype "passive"))
      (node (ref "R102") (pin "1") (pinfunction "1_1") (pintype "passive"))
      (node (ref "R3") (pin "1") (pinfunction "1_1") (pintype "passive"))
      (node (ref "R8") (pin "1") (pinfunction "1_1") (pintype "passive"))
      (node (ref "U17") (pin "2") (pinfunction "Vin_2") (pintype "power_in"))
      (node (ref "U17") (pin "3") (pinfunction "Vin_3") (pintype "power_in"))
      (node (ref "U22") (pin "5") (pinfunction "VCC_5") (pintype "power_in"))
      (node (ref "U3") (pin "2") (pinfunction "Vin_2") (pintype "power_in"))
      (node (ref "U3") (pin "3") (pinfunction "Vin_3") (pintype "power_in"))
      (node (ref "U8") (pin "2") (pinfunction "Vin_2") (pintype "power_in"))
      (node (ref "U8") (pin "3") (pinfunction "Vin_3") (pintype "power_in"))
    )
    (net (code "8") (name "+Vcore") (class "Default")
      (node (ref "C11") (pin "1") (pinfunction "1_1") (pintype "passive"))
      (node (ref "CT10") (pin "1") (pinfunction "1_1") (pintype "passive"))
      (node (ref "CT11") (pin "1") (pinfunction "1_1") (pintype "passive"))
      (node (ref "CT12") (pin "1") (pinfunction "1_1") (pintype "passive"))
      (node (ref "CT7") (pin "1") (pinfunction "1_1") (pintype "passive"))
      (node (ref "CT8") (pin "1") (pinfunction "1_1") (pintype "passive"))
      (node (ref "CT9") (pin "1") (pinfunction "1_1") (pintype "passive"))
      (node (ref "R11") (pin "1") (pinfunction "1_1") (pintype "passive"))
      (node (ref "U9") (pin "2") (pinfunction "Vin_2") (pintype "power_in"))
      (node (ref "U9") (pin "3") (pinfunction "Vin_3") (pintype "power_in"))
      (node (ref "VCORE") (pin "1") (pinfunction "In_1") (pintype "passive"))
    )
    (net (code "9") (name "/FB12") (class "Default")
      (node (ref "R10") (pin "2") (pinfunction "2_2") (pintype "passive"))
      (node (ref "R12") (pin "1") (pinfunction "1_1") (pintype "passive"))
      (node (ref "U9") (pin "7") (pinfunction "Adj_7") (pintype "input"))
    )
    (net (code "10") (name "/FB15") (class "Default")
      (node (ref "R2") (pin "2") (pinfunction "2_2") (pintype "passive"))
      (node (ref "R6") (pin "1") (pinfunction "1_1") (pintype "passive"))
      (node (ref "U7") (pin "7") (pinfunction "Adj_7") (pintype "input"))
    )
    (net (code "11") (name "/FB15A") (class "Default")
      (node (ref "R104") (pin "2") (pinfunction "2_2") (pintype "passive"))
      (node (ref "R106") (pin "1") (pinfunction "1_1") (pintype "passive"))
      (node (ref "U21") (pin "7") (pinfunction "Adj_7") (pintype "input"))
    )
    (net (code "12") (name "/FB18") (class "Default")
      (node (ref "R7") (pin "2") (pinfunction "2_2") (pintype "passive"))
      (node (ref "R9") (pin "1") (pinfunction "1_1") (pintype "passive"))
      (node (ref "U8") (pin "7") (pinfunction "Adj_7") (pintype "input"))
    )
    (net (code "13") (name "/FB25_AUX") (class "Default")
      (node (ref "R1") (pin "2") (pinfunction "2_2") (pintype "passive"))
      (node (ref "R5") (pin "1") (pinfunction "1_1") (pintype "passive"))
      (node (ref "U3") (pin "7") (pinfunction "Adj_7") (pintype "input"))
    )
    (net (code "14") (name "/FB25_SFP") (class "Default")
      (node (ref "R101") (pin "2") (pinfunction "2_2") (pintype "passive"))
      (node (ref "R103") (pin "1") (pinfunction "1_1") (pintype "passive"))
      (node (ref "U17") (pin "7") (pinfunction "Adj_7") (pintype "input"))
    )
    (net (code "15") (name "/en_1v2") (class "Default")
      (node (ref "C12") (pin "1") (pinfunction "1_1") (pintype "passive"))
      (node (ref "R11") (pin "2") (pinfunction "2_2") (pintype "passive"))
      (node (ref "U9") (pin "1") (pinfunction "En_1") (pintype "input"))
    )
    (net (code "16") (name "/en_1v5") (class "Default")
      (node (ref "C6") (pin "1") (pinfunction "1_1") (pintype "passive"))
      (node (ref "R4") (pin "2") (pinfunction "2_2") (pintype "passive"))
      (node (ref "U7") (pin "1") (pinfunction "En_1") (pintype "input"))
    )
    (net (code "17") (name "/en_1v5a") (class "Default")
      (node (ref "C161") (pin "1") (pinfunction "1_1") (pintype "passive"))
      (node (ref "R105") (pin "2") (pinfunction "2_2") (pintype "passive"))
      (node (ref "U21") (pin "1") (pinfunction "En_1") (pintype "input"))
    )
    (net (code "18") (name "/en_1v8") (class "Default")
      (node (ref "C9") (pin "1") (pinfunction "1_1") (pintype "passive"))
      (node (ref "R8") (pin "2") (pinfunction "2_2") (pintype "passive"))
      (node (ref "U8") (pin "1") (pinfunction "En_1") (pintype "input"))
    )
    (net (code "19") (name "/en_2v5") (class "Default")
      (node (ref "C4") (pin "1") (pinfunction "1_1") (pintype "passive"))
      (node (ref "R3") (pin "2") (pinfunction "2_2") (pintype "passive"))
      (node (ref "U3") (pin "1") (pinfunction "En_1") (pintype "input"))
    )
    (net (code "20") (name "/en_2v5_sfp") (class "Default")
      (node (ref "C158") (pin "1") (pinfunction "1_1") (pintype "passive"))
      (node (ref "J7") (pin "1") (pinfunction "1_1") (pintype "passive"))
      (node (ref "R102") (pin "2") (pinfunction "2_2") (pintype "passive"))
      (node (ref "U17") (pin "1") (pinfunction "En_1") (pintype "input"))
      (node (ref "U22") (pin "4") (pinfunction "Y_4") (pintype "open_collector"))
    )
    (net (code "21") (name "/en_2v5_sfp_xfpga") (class "Default")
      (node (ref "U22") (pin "2") (pinfunction "A_2") (pintype "input"))
    )
    (net (code "22") (name "GND") (class "Default")
      (node (ref "C1") (pin "2") (pinfunction "2_2") (pintype "passive"))
      (node (ref "C10") (pin "2") (pinfunction "2_2") (pintype "passive"))
      (node (ref "C11") (pin "2") (pinfunction "2_2") (pintype "passive"))
      (node (ref "C12") (pin "2") (pinfunction "2_2") (pintype "passive"))
      (node (ref "C156") (pin "2") (pinfunction "2_2") (pintype "passive"))
      (node (ref "C157") (pin "2") (pinfunction "2_2") (pintype "passive"))
      (node (ref "C158") (pin "2") (pinfunction "2_2") (pintype "passive"))
      (node (ref "C159") (pin "2") (pinfunction "2_2") (pintype "passive"))
      (node (ref "C160") (pin "2") (pinfunction "2_2") (pintype "passive"))
      (node (ref "C161") (pin "2") (pinfunction "2_2") (pintype "passive"))
      (node (ref "C162") (pin "2") (pinfunction "2_2") (pintype "passive"))
      (node (ref "C2") (pin "2") (pinfunction "2_2") (pintype "passive"))
      (node (ref "C3") (pin "2") (pinfunction "2_2") (pintype "passive"))
      (node (ref "C4") (pin "2") (pinfunction "2_2") (pintype "passive"))
      (node (ref "C5") (pin "2") (pinfunction "2_2") (pintype "passive"))
      (node (ref "C6") (pin "2") (pinfunction "2_2") (pintype "passive"))
      (node (ref "C7") (pin "2") (pinfunction "2_2") (pintype "passive"))
      (node (ref "C8") (pin "2") (pinfunction "2_2") (pintype "passive"))
      (node (ref "C9") (pin "2") (pinfunction "2_2") (pintype "passive"))
      (node (ref "CT1") (pin "2") (pinfunction "2_2") (pintype "passive"))
      (node (ref "CT10") (pin "2") (pinfunction "2_2") (pintype "passive"))
      (node (ref "CT11") (pin "2") (pinfunction "2_2") (pintype "passive"))
      (node (ref "CT12") (pin "2") (pinfunction "2_2") (pintype "passive"))
      (node (ref "CT2") (pin "2") (pinfunction "2_2") (pintype "passive"))
      (node (ref "CT3") (pin "2") (pinfunction "2_2") (pintype "passive"))
      (node (ref "CT4") (pin "2") (pinfunction "2_2") (pintype "passive"))
      (node (ref "CT5") (pin "2") (pinfunction "2_2") (pintype "passive"))
      (node (ref "CT6") (pin "2") (pinfunction "2_2") (pintype "passive"))
      (node (ref "CT7") (pin "2") (pinfunction "2_2") (pintype "passive"))
      (node (ref "CT8") (pin "2") (pinfunction "2_2") (pintype "passive"))
      (node (ref "CT9") (pin "2") (pinfunction "2_2") (pintype "passive"))
      (node (ref "J7") (pin "2") (pinfunction "2_2") (pintype "passive"))
      (node (ref "R103") (pin "2") (pinfunction "2_2") (pintype "passive"))
      (node (ref "R106") (pin "2") (pinfunction "2_2") (pintype "passive"))
      (node (ref "R12") (pin "2") (pinfunction "2_2") (pintype "passive"))
      (node (ref "R5") (pin "2") (pinfunction "2_2") (pintype "passive"))
      (node (ref "R6") (pin "2") (pinfunction "2_2") (pintype "passive"))
      (node (ref "R9") (pin "2") (pinfunction "2_2") (pintype "passive"))
      (node (ref "U17") (pin "4") (pinfunction "Gnd_4") (pintype "power_in"))
      (node (ref "U17") (pin "8") (pinfunction "Tab_8") (pintype "power_in"))
      (node (ref "U21") (pin "4") (pinfunction "Gnd_4") (pintype "power_in"))
      (node (ref "U21") (pin "8") (pinfunction "Tab_8") (pintype "power_in"))
      (node (ref "U22") (pin "3") (pinfunction "GND_3") (pintype "power_in"))
      (node (ref "U3") (pin "4") (pinfunction "Gnd_4") (pintype "power_in"))
      (node (ref "U3") (pin "8") (pinfunction "Tab_8") (pintype "power_in"))
      (node (ref "U7") (pin "4") (pinfunction "Gnd_4") (pintype "power_in"))
      (node (ref "U7") (pin "8") (pinfunction "Tab_8") (pintype "power_in"))
      (node (ref "U8") (pin "4") (pinfunction "Gnd_4") (pintype "power_in"))
      (node (ref "U8") (pin "8") (pinfunction "Tab_8") (pintype "power_in"))
      (node (ref "U9") (pin "4") (pinfunction "Gnd_4") (pintype "power_in"))
      (node (ref "U9") (pin "8") (pinfunction "Tab_8") (pintype "power_in"))
    )
    (net (code "23") (name "unconnected-(U22B-NC-Pad1)") (class "Default")
      (node (ref "U22") (pin "1") (pinfunction "NC_1") (pintype "passive"))
    )
  )
)
